# P02-DC_JACK.net
KiCad netlist of a schematic drawn in Altium Designer
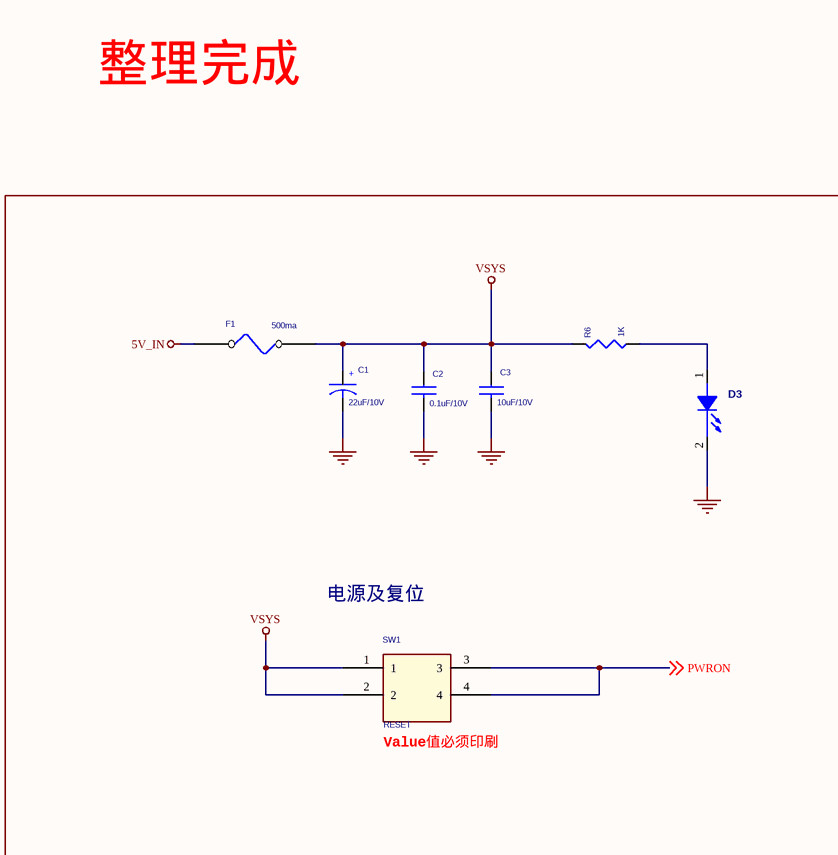
[diagram p0: P02-DC_JACK.SchDoc, top left]
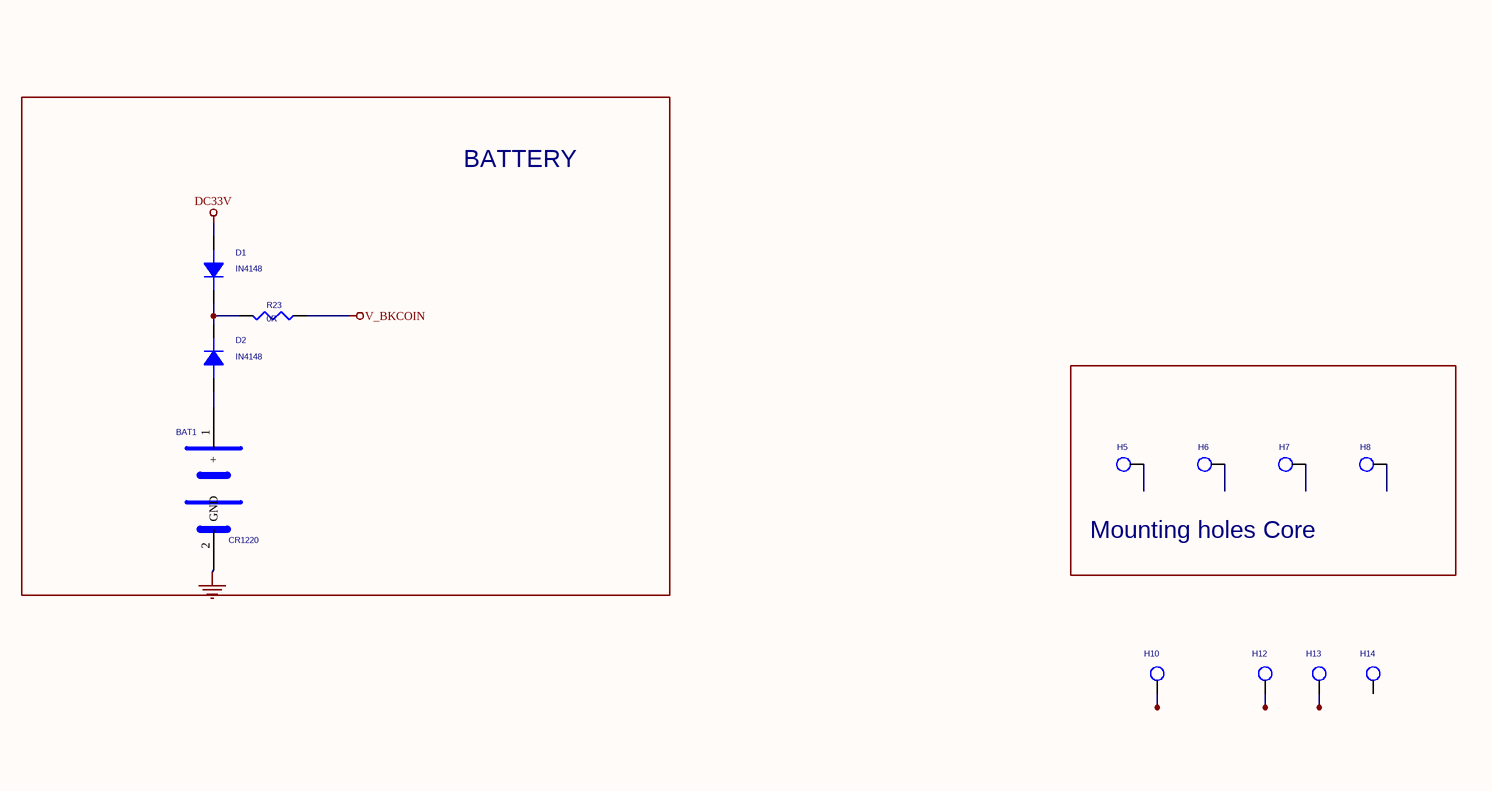
[diagram p1: P02-DC_JACK.SchDoc, top right]
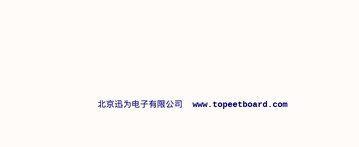
[diagram p2: P02-DC_JACK.SchDoc, bottom right]

(export (version "E")
  (design (tool "Eeschema 10.0.6"))
  (components
    (comp (ref "BAT1") (value "CR1220") (footprint "BAT1") (libsource (lib "*") (part "BATTERY_0")))
    (comp (ref "C1") (value "22uF/10V") (footprint "C1206-S") (libsource (lib "*") (part "CT2012_0")))
    (comp (ref "C2") (value "0.1uF/10V") (footprint "C0603-S") (libsource (lib "*") (part "C1608_Dup1")))
    (comp (ref "C3") (value "10uF/10V") (footprint "C0603-S") (libsource (lib "*") (part "C1608_Dup1")))
    (comp (ref "D1") (value "IN4148") (libsource (lib "*") (part "DIODE")))
    (comp (ref "D2") (value "IN4148") (libsource (lib "*") (part "DIODE")))
    (comp (ref "D3")
      (value "LED-Red (SMD 2012)")
      (footprint "LED0603")
      (libsource (lib "*") (part "LED-RED_SMD_1"))
    )
    (comp (ref "F1") (value "500ma") (libsource (lib "*") (part "FUSE")))
    (comp (ref "H5") (value "TP_P0_0.8_D0") (footprint "HOLE2_7") (libsource (lib "*") (part "TP_P0_0.8_D0")))
    (comp (ref "H6") (value "TP_P0_0.8_D0") (libsource (lib "*") (part "TP_P0_0.8_D0")))
    (comp (ref "H7") (value "TP_P0_0.8_D0") (libsource (lib "*") (part "TP_P0_0.8_D0")))
    (comp (ref "H8") (value "TP_P0_0.8_D0") (libsource (lib "*") (part "TP_P0_0.8_D0")))
    (comp (ref "H10")
      (value "TP_P0_0.8_D0")
      (footprint "HOLE2_7")
      (libsource (lib "*") (part "TP_P0_0.8_D0"))
    )
    (comp (ref "H12")
      (value "TP_P0_0.8_D0")
      (footprint "HOLE2_7")
      (libsource (lib "*") (part "TP_P0_0.8_D0"))
    )
    (comp (ref "H13")
      (value "TP_P0_0.8_D0")
      (footprint "HOLE2_7")
      (libsource (lib "*") (part "TP_P0_0.8_D0"))
    )
    (comp (ref "H14")
      (value "TP_P0_0.8_D0")
      (footprint "HOLE2_7")
      (libsource (lib "*") (part "TP_P0_0.8_D0"))
    )
    (comp (ref "R6") (value "1K") (footprint "R0603-S") (libsource (lib "*") (part "R1005_0_Dup1")))
    (comp (ref "R23") (value "0R") (libsource (lib "*") (part "R")))
    (comp (ref "SW1") (value "RESET") (footprint "SW4-SMD") (libsource (lib "*") (part "SW-4")))
  )
  (nets
    (net (code "1") (name "5V_IN") (class "Default")
      (node (ref "F1") (pin "1") (pinfunction "1_1") (pintype "passive"))
    )
    (net (code "2") (name "DC33V") (class "Default")
      (node (ref "D1") (pin "1") (pinfunction "A_1") (pintype "passive"))
    )
    (net (code "3") (name "GND") (class "Default")
      (node (ref "BAT1") (pin "2") (pinfunction "GND_2") (pintype "passive"))
      (node (ref "C1") (pin "2") (pinfunction "2_2") (pintype "passive"))
      (node (ref "C2") (pin "2") (pinfunction "2_2") (pintype "passive"))
      (node (ref "C3") (pin "2") (pinfunction "2_2") (pintype "passive"))
      (node (ref "D3") (pin "2") (pinfunction "CATHODE_2") (pintype "passive"))
    )
    (net (code "4") (name "Net-(BAT1-+)") (class "Default")
      (node (ref "BAT1") (pin "1") (pinfunction "+_1") (pintype "passive"))
      (node (ref "D2") (pin "1") (pinfunction "A_1") (pintype "passive"))
    )
    (net (code "5") (name "Net-(D1-K)") (class "Default")
      (node (ref "D1") (pin "2") (pinfunction "K_2") (pintype "passive"))
      (node (ref "D2") (pin "2") (pinfunction "K_2") (pintype "passive"))
      (node (ref "R23") (pin "2") (pinfunction "2_2") (pintype "passive"))
    )
    (net (code "6") (name "Net-(D3-ANODE)") (class "Default")
      (node (ref "D3") (pin "1") (pinfunction "ANODE_1") (pintype "passive"))
      (node (ref "R6") (pin "1") (pinfunction "1_1") (pintype "passive"))
    )
    (net (code "7") (name "PWRON") (class "Default")
      (node (ref "SW1") (pin "3") (pinfunction "3_3") (pintype "passive"))
      (node (ref "SW1") (pin "4") (pinfunction "4_4") (pintype "passive"))
    )
    (net (code "8") (name "VSYS") (class "Default")
      (node (ref "C1") (pin "1") (pinfunction "1_1") (pintype "passive"))
      (node (ref "C2") (pin "1") (pinfunction "1_1") (pintype "passive"))
      (node (ref "C3") (pin "1") (pinfunction "1_1") (pintype "passive"))
      (node (ref "F1") (pin "2") (pinfunction "2_2") (pintype "passive"))
      (node (ref "R6") (pin "2") (pinfunction "2_2") (pintype "passive"))
      (node (ref "SW1") (pin "1") (pinfunction "1_1") (pintype "passive"))
      (node (ref "SW1") (pin "2") (pinfunction "2_2") (pintype "passive"))
    )
    (net (code "9") (name "V_BKCOIN") (class "Default")
      (node (ref "R23") (pin "1") (pinfunction "1_1") (pintype "passive"))
    )
    (net (code "10") (name "unconnected-(H5-Pad1)") (class "Default")
      (node (ref "H5") (pin "1") (pinfunction "1_1") (pintype "passive"))
    )
    (net (code "11") (name "unconnected-(H6-Pad1)") (class "Default")
      (node (ref "H6") (pin "1") (pinfunction "1_1") (pintype "passive"))
    )
    (net (code "12") (name "unconnected-(H7-Pad1)") (class "Default")
      (node (ref "H7") (pin "1") (pinfunction "1_1") (pintype "passive"))
    )
    (net (code "13") (name "unconnected-(H8-Pad1)") (class "Default")
      (node (ref "H8") (pin "1") (pinfunction "1_1") (pintype "passive"))
    )
    (net (code "14") (name "unconnected-(H10-Pad1)") (class "Default")
      (node (ref "H10") (pin "1") (pinfunction "1_1") (pintype "passive"))
    )
    (net (code "15") (name "unconnected-(H12-Pad1)") (class "Default")
      (node (ref "H12") (pin "1") (pinfunction "1_1") (pintype "passive"))
    )
    (net (code "16") (name "unconnected-(H13-Pad1)") (class "Default")
      (node (ref "H13") (pin "1") (pinfunction "1_1") (pintype "passive"))
    )
    (net (code "17") (name "unconnected-(H14-Pad1)") (class "Default")
      (node (ref "H14") (pin "1") (pinfunction "1_1") (pintype "passive"))
    )
  )
)
